# RainbowCycle.net
KiCad netlist of a schematic drawn in EAGLE
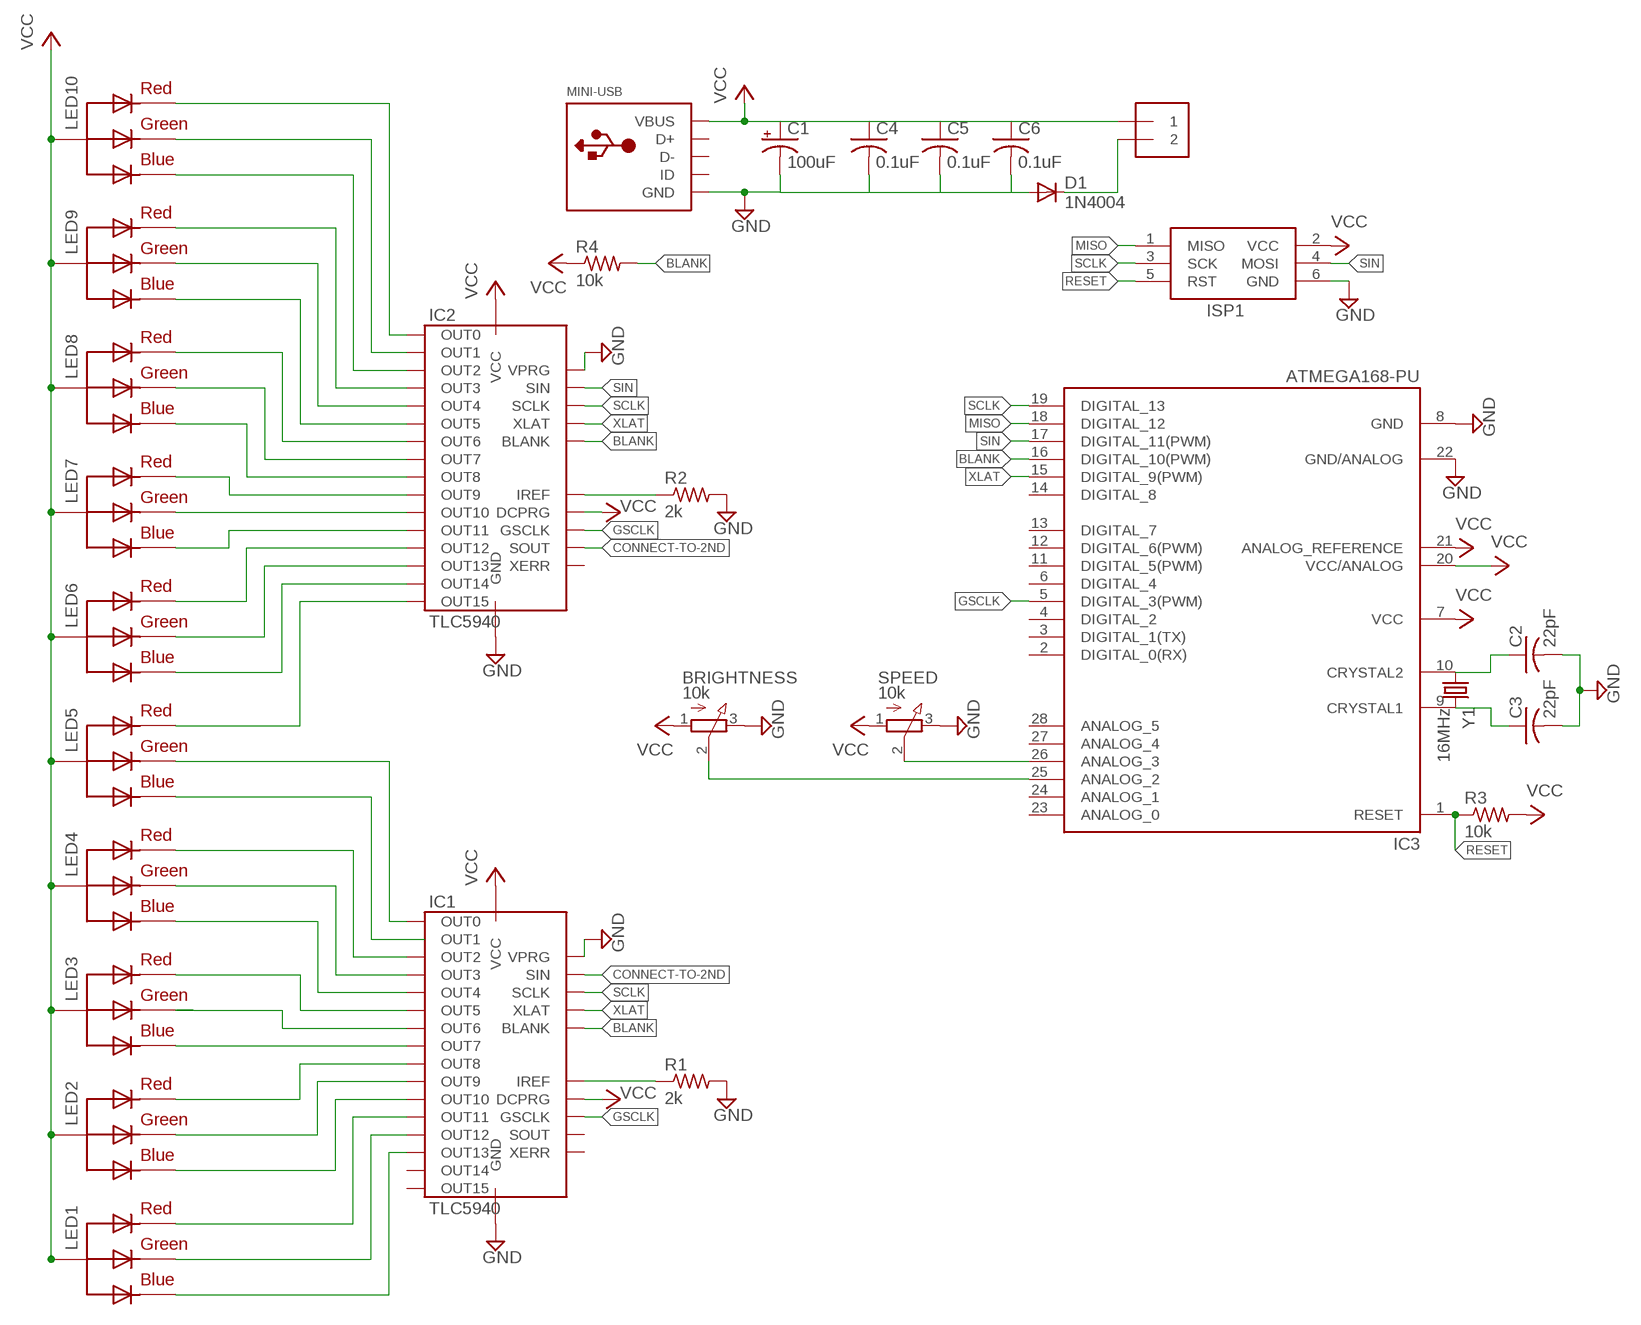
[diagram p0: schematic, sheet 1]

(export (version "E")
  (design (tool "Eeschema 10.0.6"))
  (components
    (comp (ref "BLOCK-TERMINAL")
      (value "1X2-5.08MM")
      (footprint "eagle-import:1X2-5.08MM")
      (libsource (lib "eagle-import") (part "1X2-5.08MM"))
    )
    (comp (ref "BRIGHTNESS")
      (value "10k")
      (footprint "eagle-import:3RP_1610N")
      (libsource (lib "eagle-import") (part "3RP/1610N"))
    )
    (comp (ref "C1")
      (value "100uF")
      (footprint "eagle-import:E2,5-6")
      (libsource (lib "eagle-import") (part "CPOL-USE2.5-6"))
    )
    (comp (ref "C2")
      (value "22pF")
      (footprint "eagle-import:C050-025X075")
      (libsource (lib "eagle-import") (part "C-US050-025X075"))
    )
    (comp (ref "C3")
      (value "22pF")
      (footprint "eagle-import:C050-025X075")
      (libsource (lib "eagle-import") (part "C-US050-025X075"))
    )
    (comp (ref "C4")
      (value "0.1uF")
      (footprint "eagle-import:C050-025X075")
      (libsource (lib "eagle-import") (part "C-US050-025X075"))
    )
    (comp (ref "C5")
      (value "0.1uF")
      (footprint "eagle-import:C050-025X075")
      (libsource (lib "eagle-import") (part "C-US050-025X075"))
    )
    (comp (ref "C6")
      (value "0.1uF")
      (footprint "eagle-import:C050-025X075")
      (libsource (lib "eagle-import") (part "C-US050-025X075"))
    )
    (comp (ref "D1")
      (value "1N4004")
      (footprint "eagle-import:DO41-10")
      (libsource (lib "eagle-import") (part "1N4004"))
    )
    (comp (ref "IC1")
      (value "TLC5940")
      (footprint "eagle-import:IC-PACKAGE_DIL28-3")
      (libsource (lib "eagle-import") (part "IC-PACKAGE_DIL28-3"))
    )
    (comp (ref "IC2")
      (value "TLC5940")
      (footprint "eagle-import:IC-PACKAGE_DIL28-3")
      (libsource (lib "eagle-import") (part "IC-PACKAGE_DIL28-3"))
    )
    (comp (ref "IC3")
      (value "ATMEGA168-PU")
      (footprint "eagle-import:DIL28-3")
      (libsource (lib "eagle-import") (part "ATMEGA168-PU"))
    )
    (comp (ref "ISP1")
      (value "AVRISP-6")
      (footprint "eagle-import:AVRISP")
      (libsource (lib "eagle-import") (part "AVRISP-6"))
    )
    (comp (ref "LED1")
      (value "RGBLED_CA")
      (footprint "eagle-import:PIRANHA5MM")
      (libsource (lib "eagle-import") (part "RGBLED_CA-PIRANHA"))
    )
    (comp (ref "LED2")
      (value "RGBLED_CA")
      (footprint "eagle-import:PIRANHA5MM")
      (libsource (lib "eagle-import") (part "RGBLED_CA-PIRANHA"))
    )
    (comp (ref "LED3")
      (value "RGBLED_CA")
      (footprint "eagle-import:PIRANHA5MM")
      (libsource (lib "eagle-import") (part "RGBLED_CA-PIRANHA"))
    )
    (comp (ref "LED4")
      (value "RGBLED_CA")
      (footprint "eagle-import:PIRANHA5MM")
      (libsource (lib "eagle-import") (part "RGBLED_CA-PIRANHA"))
    )
    (comp (ref "LED5")
      (value "RGBLED_CA")
      (footprint "eagle-import:PIRANHA5MM")
      (libsource (lib "eagle-import") (part "RGBLED_CA-PIRANHA"))
    )
    (comp (ref "LED6")
      (value "RGBLED_CA")
      (footprint "eagle-import:PIRANHA5MM")
      (libsource (lib "eagle-import") (part "RGBLED_CA-PIRANHA"))
    )
    (comp (ref "LED7")
      (value "RGBLED_CA")
      (footprint "eagle-import:PIRANHA5MM")
      (libsource (lib "eagle-import") (part "RGBLED_CA-PIRANHA"))
    )
    (comp (ref "LED8")
      (value "RGBLED_CA")
      (footprint "eagle-import:PIRANHA5MM")
      (libsource (lib "eagle-import") (part "RGBLED_CA-PIRANHA"))
    )
    (comp (ref "LED9")
      (value "RGBLED_CA")
      (footprint "eagle-import:PIRANHA5MM")
      (libsource (lib "eagle-import") (part "RGBLED_CA-PIRANHA"))
    )
    (comp (ref "LED10")
      (value "RGBLED_CA")
      (footprint "eagle-import:PIRANHA5MM")
      (libsource (lib "eagle-import") (part "RGBLED_CA-PIRANHA"))
    )
    (comp (ref "MINI-USB")
      (value "USBMOLEX")
      (footprint "eagle-import:USB-MINIB-THM-MOLEX")
      (libsource (lib "eagle-import") (part "USBMOLEX"))
    )
    (comp (ref "R1")
      (value "2k")
      (footprint "eagle-import:0207_10")
      (libsource (lib "eagle-import") (part "R-US_0207/10"))
    )
    (comp (ref "R2")
      (value "2k")
      (footprint "eagle-import:0207_10")
      (libsource (lib "eagle-import") (part "R-US_0207/10"))
    )
    (comp (ref "R3")
      (value "10k")
      (footprint "eagle-import:0207_10")
      (libsource (lib "eagle-import") (part "R-US_0207/10"))
    )
    (comp (ref "R4")
      (value "10k")
      (footprint "eagle-import:0207_10")
      (libsource (lib "eagle-import") (part "R-US_0207/10"))
    )
    (comp (ref "SPEED")
      (value "10k")
      (footprint "eagle-import:3RP_1610N")
      (libsource (lib "eagle-import") (part "3RP/1610N"))
    )
    (comp (ref "Y1")
      (value "16MHz")
      (footprint "eagle-import:HC49US")
      (libsource (lib "eagle-import") (part "CRYSTALHC49US"))
    )
  )
  (nets
    (net (code "1") (name "BLANK") (class "Default")
      (node (ref "IC1") (pin "23") (pinfunction "BLANK_23") (pintype "input"))
      (node (ref "IC2") (pin "23") (pinfunction "BLANK_23") (pintype "input"))
      (node (ref "IC3") (pin "16") (pinfunction "DIGITAL_10(PWM)_16") (pintype "bidirectional"))
      (node (ref "R4") (pin "2") (pinfunction "2_2") (pintype "passive"))
    )
    (net (code "2") (name "CONNECT-TO-2ND") (class "Default")
      (node (ref "IC1") (pin "26") (pinfunction "SIN_26") (pintype "input"))
      (node (ref "IC2") (pin "17") (pinfunction "SOUT_17") (pintype "output"))
    )
    (net (code "3") (name "GND") (class "Default")
      (node (ref "BRIGHTNESS") (pin "3") (pinfunction "E_3") (pintype "passive"))
      (node (ref "C1") (pin "-") (pinfunction "-_-") (pintype "passive"))
      (node (ref "C2") (pin "2") (pinfunction "2_2") (pintype "passive"))
      (node (ref "C3") (pin "2") (pinfunction "2_2") (pintype "passive"))
      (node (ref "C4") (pin "2") (pinfunction "2_2") (pintype "passive"))
      (node (ref "C5") (pin "2") (pinfunction "2_2") (pintype "passive"))
      (node (ref "C6") (pin "2") (pinfunction "2_2") (pintype "passive"))
      (node (ref "D1") (pin "A") (pinfunction "A_A") (pintype "passive"))
      (node (ref "IC1") (pin "22") (pinfunction "GND_22") (pintype "power_in"))
      (node (ref "IC1") (pin "27") (pinfunction "VPRG_27") (pintype "input"))
      (node (ref "IC2") (pin "22") (pinfunction "GND_22") (pintype "power_in"))
      (node (ref "IC2") (pin "27") (pinfunction "VPRG_27") (pintype "input"))
      (node (ref "IC3") (pin "22") (pinfunction "GND/ANALOG_22") (pintype "power_in"))
      (node (ref "IC3") (pin "8") (pinfunction "GND_8") (pintype "power_in"))
      (node (ref "ISP1") (pin "6") (pinfunction "GND_6") (pintype "power_in"))
      (node (ref "MINI-USB") (pin "GND") (pinfunction "GND_GND") (pintype "power_in"))
      (node (ref "MINI-USB") (pin "GND1") (pinfunction "GND_GND1") (pintype "power_in"))
      (node (ref "MINI-USB") (pin "GND4") (pinfunction "GND_GND4") (pintype "power_in"))
      (node (ref "R1") (pin "2") (pinfunction "2_2") (pintype "passive"))
      (node (ref "R2") (pin "2") (pinfunction "2_2") (pintype "passive"))
      (node (ref "SPEED") (pin "3") (pinfunction "E_3") (pintype "passive"))
    )
    (net (code "4") (name "GSCLK") (class "Default")
      (node (ref "IC1") (pin "18") (pinfunction "GSCLK_18") (pintype "input"))
      (node (ref "IC2") (pin "18") (pinfunction "GSCLK_18") (pintype "input"))
      (node (ref "IC3") (pin "5") (pinfunction "DIGITAL_3(PWM)_5") (pintype "bidirectional"))
    )
    (net (code "5") (name "MISO") (class "Default")
      (node (ref "IC3") (pin "18") (pinfunction "DIGITAL_12_18") (pintype "bidirectional"))
      (node (ref "ISP1") (pin "1") (pinfunction "MISO_1") (pintype "input"))
    )
    (net (code "6") (name "Net-(BLOCK-TERMINAL-Pad2)") (class "Default")
      (node (ref "BLOCK-TERMINAL") (pin "2") (pinfunction "2_2") (pintype "passive"))
      (node (ref "D1") (pin "C") (pinfunction "C_C") (pintype "passive"))
    )
    (net (code "7") (name "Net-(BRIGHTNESS-S)") (class "Default")
      (node (ref "BRIGHTNESS") (pin "2") (pinfunction "S_2") (pintype "passive"))
      (node (ref "IC3") (pin "25") (pinfunction "ANALOG_2_25") (pintype "bidirectional"))
    )
    (net (code "8") (name "Net-(IC1-IREF)") (class "Default")
      (node (ref "IC1") (pin "20") (pinfunction "IREF_20") (pintype "passive"))
      (node (ref "R1") (pin "1") (pinfunction "1_1") (pintype "passive"))
    )
    (net (code "9") (name "Net-(IC1-OUT0)") (class "Default")
      (node (ref "IC1") (pin "28") (pinfunction "OUT0_28") (pintype "open_collector"))
      (node (ref "LED5") (pin "2") (pinfunction "GREEN_2") (pintype "bidirectional"))
    )
    (net (code "10") (name "Net-(IC1-OUT1)") (class "Default")
      (node (ref "IC1") (pin "1") (pinfunction "OUT1_1") (pintype "open_collector"))
      (node (ref "LED5") (pin "1") (pinfunction "BLUE_1") (pintype "bidirectional"))
    )
    (net (code "11") (name "Net-(IC1-OUT2)") (class "Default")
      (node (ref "IC1") (pin "2") (pinfunction "OUT2_2") (pintype "open_collector"))
      (node (ref "LED4") (pin "3") (pinfunction "RED_3") (pintype "bidirectional"))
    )
    (net (code "12") (name "Net-(IC1-OUT3)") (class "Default")
      (node (ref "IC1") (pin "3") (pinfunction "OUT3_3") (pintype "open_collector"))
      (node (ref "LED4") (pin "2") (pinfunction "GREEN_2") (pintype "bidirectional"))
    )
    (net (code "13") (name "Net-(IC1-OUT4)") (class "Default")
      (node (ref "IC1") (pin "4") (pinfunction "OUT4_4") (pintype "open_collector"))
      (node (ref "LED4") (pin "1") (pinfunction "BLUE_1") (pintype "bidirectional"))
    )
    (net (code "14") (name "Net-(IC1-OUT5)") (class "Default")
      (node (ref "IC1") (pin "5") (pinfunction "OUT5_5") (pintype "open_collector"))
      (node (ref "LED3") (pin "3") (pinfunction "RED_3") (pintype "bidirectional"))
    )
    (net (code "15") (name "Net-(IC1-OUT6)") (class "Default")
      (node (ref "IC1") (pin "6") (pinfunction "OUT6_6") (pintype "open_collector"))
      (node (ref "LED3") (pin "2") (pinfunction "GREEN_2") (pintype "bidirectional"))
    )
    (net (code "16") (name "Net-(IC1-OUT7)") (class "Default")
      (node (ref "IC1") (pin "7") (pinfunction "OUT7_7") (pintype "open_collector"))
      (node (ref "LED3") (pin "1") (pinfunction "BLUE_1") (pintype "bidirectional"))
    )
    (net (code "17") (name "Net-(IC1-OUT8)") (class "Default")
      (node (ref "IC1") (pin "8") (pinfunction "OUT8_8") (pintype "open_collector"))
      (node (ref "LED2") (pin "3") (pinfunction "RED_3") (pintype "bidirectional"))
    )
    (net (code "18") (name "Net-(IC1-OUT9)") (class "Default")
      (node (ref "IC1") (pin "9") (pinfunction "OUT9_9") (pintype "open_collector"))
      (node (ref "LED2") (pin "2") (pinfunction "GREEN_2") (pintype "bidirectional"))
    )
    (net (code "19") (name "Net-(IC1-OUT10)") (class "Default")
      (node (ref "IC1") (pin "10") (pinfunction "OUT10_10") (pintype "open_collector"))
      (node (ref "LED2") (pin "1") (pinfunction "BLUE_1") (pintype "bidirectional"))
    )
    (net (code "20") (name "Net-(IC1-OUT11)") (class "Default")
      (node (ref "IC1") (pin "11") (pinfunction "OUT11_11") (pintype "open_collector"))
      (node (ref "LED1") (pin "3") (pinfunction "RED_3") (pintype "bidirectional"))
    )
    (net (code "21") (name "Net-(IC1-OUT12)") (class "Default")
      (node (ref "IC1") (pin "12") (pinfunction "OUT12_12") (pintype "open_collector"))
      (node (ref "LED1") (pin "2") (pinfunction "GREEN_2") (pintype "bidirectional"))
    )
    (net (code "22") (name "Net-(IC1-OUT13)") (class "Default")
      (node (ref "IC1") (pin "13") (pinfunction "OUT13_13") (pintype "open_collector"))
      (node (ref "LED1") (pin "1") (pinfunction "BLUE_1") (pintype "bidirectional"))
    )
    (net (code "23") (name "Net-(IC2-IREF)") (class "Default")
      (node (ref "IC2") (pin "20") (pinfunction "IREF_20") (pintype "passive"))
      (node (ref "R2") (pin "1") (pinfunction "1_1") (pintype "passive"))
    )
    (net (code "24") (name "Net-(IC2-OUT0)") (class "Default")
      (node (ref "IC2") (pin "28") (pinfunction "OUT0_28") (pintype "open_collector"))
      (node (ref "LED10") (pin "3") (pinfunction "RED_3") (pintype "bidirectional"))
    )
    (net (code "25") (name "Net-(IC2-OUT1)") (class "Default")
      (node (ref "IC2") (pin "1") (pinfunction "OUT1_1") (pintype "open_collector"))
      (node (ref "LED10") (pin "2") (pinfunction "GREEN_2") (pintype "bidirectional"))
    )
    (net (code "26") (name "Net-(IC2-OUT2)") (class "Default")
      (node (ref "IC2") (pin "2") (pinfunction "OUT2_2") (pintype "open_collector"))
      (node (ref "LED10") (pin "1") (pinfunction "BLUE_1") (pintype "bidirectional"))
    )
    (net (code "27") (name "Net-(IC2-OUT3)") (class "Default")
      (node (ref "IC2") (pin "3") (pinfunction "OUT3_3") (pintype "open_collector"))
      (node (ref "LED9") (pin "3") (pinfunction "RED_3") (pintype "bidirectional"))
    )
    (net (code "28") (name "Net-(IC2-OUT4)") (class "Default")
      (node (ref "IC2") (pin "4") (pinfunction "OUT4_4") (pintype "open_collector"))
      (node (ref "LED9") (pin "2") (pinfunction "GREEN_2") (pintype "bidirectional"))
    )
    (net (code "29") (name "Net-(IC2-OUT5)") (class "Default")
      (node (ref "IC2") (pin "5") (pinfunction "OUT5_5") (pintype "open_collector"))
      (node (ref "LED9") (pin "1") (pinfunction "BLUE_1") (pintype "bidirectional"))
    )
    (net (code "30") (name "Net-(IC2-OUT6)") (class "Default")
      (node (ref "IC2") (pin "6") (pinfunction "OUT6_6") (pintype "open_collector"))
      (node (ref "LED8") (pin "3") (pinfunction "RED_3") (pintype "bidirectional"))
    )
    (net (code "31") (name "Net-(IC2-OUT7)") (class "Default")
      (node (ref "IC2") (pin "7") (pinfunction "OUT7_7") (pintype "open_collector"))
      (node (ref "LED8") (pin "2") (pinfunction "GREEN_2") (pintype "bidirectional"))
    )
    (net (code "32") (name "Net-(IC2-OUT8)") (class "Default")
      (node (ref "IC2") (pin "8") (pinfunction "OUT8_8") (pintype "open_collector"))
      (node (ref "LED8") (pin "1") (pinfunction "BLUE_1") (pintype "bidirectional"))
    )
    (net (code "33") (name "Net-(IC2-OUT9)") (class "Default")
      (node (ref "IC2") (pin "9") (pinfunction "OUT9_9") (pintype "open_collector"))
      (node (ref "LED7") (pin "3") (pinfunction "RED_3") (pintype "bidirectional"))
    )
    (net (code "34") (name "Net-(IC2-OUT10)") (class "Default")
      (node (ref "IC2") (pin "10") (pinfunction "OUT10_10") (pintype "open_collector"))
      (node (ref "LED7") (pin "2") (pinfunction "GREEN_2") (pintype "bidirectional"))
    )
    (net (code "35") (name "Net-(IC2-OUT11)") (class "Default")
      (node (ref "IC2") (pin "11") (pinfunction "OUT11_11") (pintype "open_collector"))
      (node (ref "LED7") (pin "1") (pinfunction "BLUE_1") (pintype "bidirectional"))
    )
    (net (code "36") (name "Net-(IC2-OUT12)") (class "Default")
      (node (ref "IC2") (pin "12") (pinfunction "OUT12_12") (pintype "open_collector"))
      (node (ref "LED6") (pin "3") (pinfunction "RED_3") (pintype "bidirectional"))
    )
    (net (code "37") (name "Net-(IC2-OUT13)") (class "Default")
      (node (ref "IC2") (pin "13") (pinfunction "OUT13_13") (pintype "open_collector"))
      (node (ref "LED6") (pin "2") (pinfunction "GREEN_2") (pintype "bidirectional"))
    )
    (net (code "38") (name "Net-(IC2-OUT14)") (class "Default")
      (node (ref "IC2") (pin "14") (pinfunction "OUT14_14") (pintype "open_collector"))
      (node (ref "LED6") (pin "1") (pinfunction "BLUE_1") (pintype "bidirectional"))
    )
    (net (code "39") (name "Net-(IC2-OUT15)") (class "Default")
      (node (ref "IC2") (pin "15") (pinfunction "OUT15_15") (pintype "open_collector"))
      (node (ref "LED5") (pin "3") (pinfunction "RED_3") (pintype "bidirectional"))
    )
    (net (code "40") (name "Net-(IC3-ANALOG_3)") (class "Default")
      (node (ref "IC3") (pin "26") (pinfunction "ANALOG_3_26") (pintype "bidirectional"))
      (node (ref "SPEED") (pin "2") (pinfunction "S_2") (pintype "passive"))
    )
    (net (code "41") (name "Net-(IC3-CRYSTAL1)") (class "Default")
      (node (ref "C3") (pin "1") (pinfunction "1_1") (pintype "passive"))
      (node (ref "IC3") (pin "9") (pinfunction "CRYSTAL1_9") (pintype "bidirectional"))
      (node (ref "Y1") (pin "2") (pinfunction "2_2") (pintype "passive"))
    )
    (net (code "42") (name "Net-(IC3-CRYSTAL2)") (class "Default")
      (node (ref "C2") (pin "1") (pinfunction "1_1") (pintype "passive"))
      (node (ref "IC3") (pin "10") (pinfunction "CRYSTAL2_10") (pintype "bidirectional"))
      (node (ref "Y1") (pin "1") (pinfunction "1_1") (pintype "passive"))
    )
    (net (code "43") (name "RESET") (class "Default")
      (node (ref "IC3") (pin "1") (pinfunction "RESET_1") (pintype "bidirectional"))
      (node (ref "ISP1") (pin "5") (pinfunction "RST_5") (pintype "output"))
      (node (ref "R3") (pin "1") (pinfunction "1_1") (pintype "passive"))
    )
    (net (code "44") (name "SCLK") (class "Default")
      (node (ref "IC1") (pin "25") (pinfunction "SCLK_25") (pintype "input"))
      (node (ref "IC2") (pin "25") (pinfunction "SCLK_25") (pintype "input"))
      (node (ref "IC3") (pin "19") (pinfunction "DIGITAL_13_19") (pintype "bidirectional"))
      (node (ref "ISP1") (pin "3") (pinfunction "SCK_3") (pintype "output"))
    )
    (net (code "45") (name "SIN") (class "Default")
      (node (ref "IC2") (pin "26") (pinfunction "SIN_26") (pintype "input"))
      (node (ref "IC3") (pin "17") (pinfunction "DIGITAL_11(PWM)_17") (pintype "bidirectional"))
      (node (ref "ISP1") (pin "4") (pinfunction "MOSI_4") (pintype "output"))
    )
    (net (code "46") (name "VCC") (class "Default")
      (node (ref "BLOCK-TERMINAL") (pin "1") (pinfunction "1_1") (pintype "passive"))
      (node (ref "BRIGHTNESS") (pin "1") (pinfunction "A_1") (pintype "passive"))
      (node (ref "C1") (pin "+") (pinfunction "+_+") (pintype "passive"))
      (node (ref "C4") (pin "1") (pinfunction "1_1") (pintype "passive"))
      (node (ref "C5") (pin "1") (pinfunction "1_1") (pintype "passive"))
      (node (ref "C6") (pin "1") (pinfunction "1_1") (pintype "passive"))
      (node (ref "IC1") (pin "19") (pinfunction "DCPRG_19") (pintype "input"))
      (node (ref "IC1") (pin "21") (pinfunction "VCC_21") (pintype "power_in"))
      (node (ref "IC2") (pin "19") (pinfunction "DCPRG_19") (pintype "input"))
      (node (ref "IC2") (pin "21") (pinfunction "VCC_21") (pintype "power_in"))
      (node (ref "IC3") (pin "20") (pinfunction "VCC/ANALOG_20") (pintype "passive"))
      (node (ref "IC3") (pin "21") (pinfunction "ANALOG_REFERENCE_21") (pintype "passive"))
      (node (ref "IC3") (pin "7") (pinfunction "VCC_7") (pintype "power_in"))
      (node (ref "ISP1") (pin "2") (pinfunction "VCC_2") (pintype "power_in"))
      (node (ref "LED1") (pin "4") (pinfunction "VCC_4") (pintype "bidirectional"))
      (node (ref "LED10") (pin "4") (pinfunction "VCC_4") (pintype "bidirectional"))
      (node (ref "LED2") (pin "4") (pinfunction "VCC_4") (pintype "bidirectional"))
      (node (ref "LED3") (pin "4") (pinfunction "VCC_4") (pintype "bidirectional"))
      (node (ref "LED4") (pin "4") (pinfunction "VCC_4") (pintype "bidirectional"))
      (node (ref "LED5") (pin "4") (pinfunction "VCC_4") (pintype "bidirectional"))
      (node (ref "LED6") (pin "4") (pinfunction "VCC_4") (pintype "bidirectional"))
      (node (ref "LED7") (pin "4") (pinfunction "VCC_4") (pintype "bidirectional"))
      (node (ref "LED8") (pin "4") (pinfunction "VCC_4") (pintype "bidirectional"))
      (node (ref "LED9") (pin "4") (pinfunction "VCC_4") (pintype "bidirectional"))
      (node (ref "MINI-USB") (pin "VBUS") (pinfunction "VBUS_VBUS") (pintype "power_in"))
      (node (ref "R3") (pin "2") (pinfunction "2_2") (pintype "passive"))
      (node (ref "R4") (pin "1") (pinfunction "1_1") (pintype "passive"))
      (node (ref "SPEED") (pin "1") (pinfunction "A_1") (pintype "passive"))
    )
    (net (code "47") (name "XLAT") (class "Default")
      (node (ref "IC1") (pin "24") (pinfunction "XLAT_24") (pintype "input"))
      (node (ref "IC2") (pin "24") (pinfunction "XLAT_24") (pintype "input"))
      (node (ref "IC3") (pin "15") (pinfunction "DIGITAL_9(PWM)_15") (pintype "bidirectional"))
    )
    (net (code "48") (name "unconnected-(IC1-OUT14-Pad14)") (class "Default")
      (node (ref "IC1") (pin "14") (pinfunction "OUT14_14") (pintype "open_collector"))
    )
    (net (code "49") (name "unconnected-(IC1-OUT15-Pad15)") (class "Default")
      (node (ref "IC1") (pin "15") (pinfunction "OUT15_15") (pintype "open_collector"))
    )
    (net (code "50") (name "unconnected-(IC1-SOUT-Pad17)") (class "Default")
      (node (ref "IC1") (pin "17") (pinfunction "SOUT_17") (pintype "output"))
    )
    (net (code "51") (name "unconnected-(IC1-XERR-Pad16)") (class "Default")
      (node (ref "IC1") (pin "16") (pinfunction "XERR_16") (pintype "open_collector"))
    )
    (net (code "52") (name "unconnected-(IC2-XERR-Pad16)") (class "Default")
      (node (ref "IC2") (pin "16") (pinfunction "XERR_16") (pintype "open_collector"))
    )
    (net (code "53") (name "unconnected-(IC3-ANALOG_0-Pad23)") (class "Default")
      (node (ref "IC3") (pin "23") (pinfunction "ANALOG_0_23") (pintype "bidirectional"))
    )
    (net (code "54") (name "unconnected-(IC3-ANALOG_1-Pad24)") (class "Default")
      (node (ref "IC3") (pin "24") (pinfunction "ANALOG_1_24") (pintype "bidirectional"))
    )
    (net (code "55") (name "unconnected-(IC3-ANALOG_4-Pad27)") (class "Default")
      (node (ref "IC3") (pin "27") (pinfunction "ANALOG_4_27") (pintype "bidirectional"))
    )
    (net (code "56") (name "unconnected-(IC3-ANALOG_5-Pad28)") (class "Default")
      (node (ref "IC3") (pin "28") (pinfunction "ANALOG_5_28") (pintype "bidirectional"))
    )
    (net (code "57") (name "unconnected-(IC3-DIGITAL_0(RX)-Pad2)") (class "Default")
      (node (ref "IC3") (pin "2") (pinfunction "DIGITAL_0(RX)_2") (pintype "bidirectional"))
    )
    (net (code "58") (name "unconnected-(IC3-DIGITAL_1(TX)-Pad3)") (class "Default")
      (node (ref "IC3") (pin "3") (pinfunction "DIGITAL_1(TX)_3") (pintype "bidirectional"))
    )
    (net (code "59") (name "unconnected-(IC3-DIGITAL_2-Pad4)") (class "Default")
      (node (ref "IC3") (pin "4") (pinfunction "DIGITAL_2_4") (pintype "bidirectional"))
    )
    (net (code "60") (name "unconnected-(IC3-DIGITAL_4-Pad6)") (class "Default")
      (node (ref "IC3") (pin "6") (pinfunction "DIGITAL_4_6") (pintype "bidirectional"))
    )
    (net (code "61") (name "unconnected-(IC3-DIGITAL_5(PWM)-Pad11)") (class "Default")
      (node (ref "IC3") (pin "11") (pinfunction "DIGITAL_5(PWM)_11") (pintype "bidirectional"))
    )
    (net (code "62") (name "unconnected-(IC3-DIGITAL_6(PWM)-Pad12)") (class "Default")
      (node (ref "IC3") (pin "12") (pinfunction "DIGITAL_6(PWM)_12") (pintype "bidirectional"))
    )
    (net (code "63") (name "unconnected-(IC3-DIGITAL_7-Pad13)") (class "Default")
      (node (ref "IC3") (pin "13") (pinfunction "DIGITAL_7_13") (pintype "bidirectional"))
    )
    (net (code "64") (name "unconnected-(IC3-DIGITAL_8-Pad14)") (class "Default")
      (node (ref "IC3") (pin "14") (pinfunction "DIGITAL_8_14") (pintype "bidirectional"))
    )
    (net (code "65") (name "unconnected-(MINI-USB-PadD+)") (class "Default")
      (node (ref "MINI-USB") (pin "D+") (pinfunction "D+_D+") (pintype "bidirectional"))
    )
    (net (code "66") (name "unconnected-(MINI-USB-PadD-)") (class "Default")
      (node (ref "MINI-USB") (pin "D-") (pinfunction "D-_D-") (pintype "bidirectional"))
    )
    (net (code "67") (name "unconnected-(MINI-USB-PadID)") (class "Default")
      (node (ref "MINI-USB") (pin "ID") (pinfunction "ID_ID") (pintype "bidirectional"))
    )
  )
)
